# display.net
KiCad netlist of a schematic drawn in Altium Designer
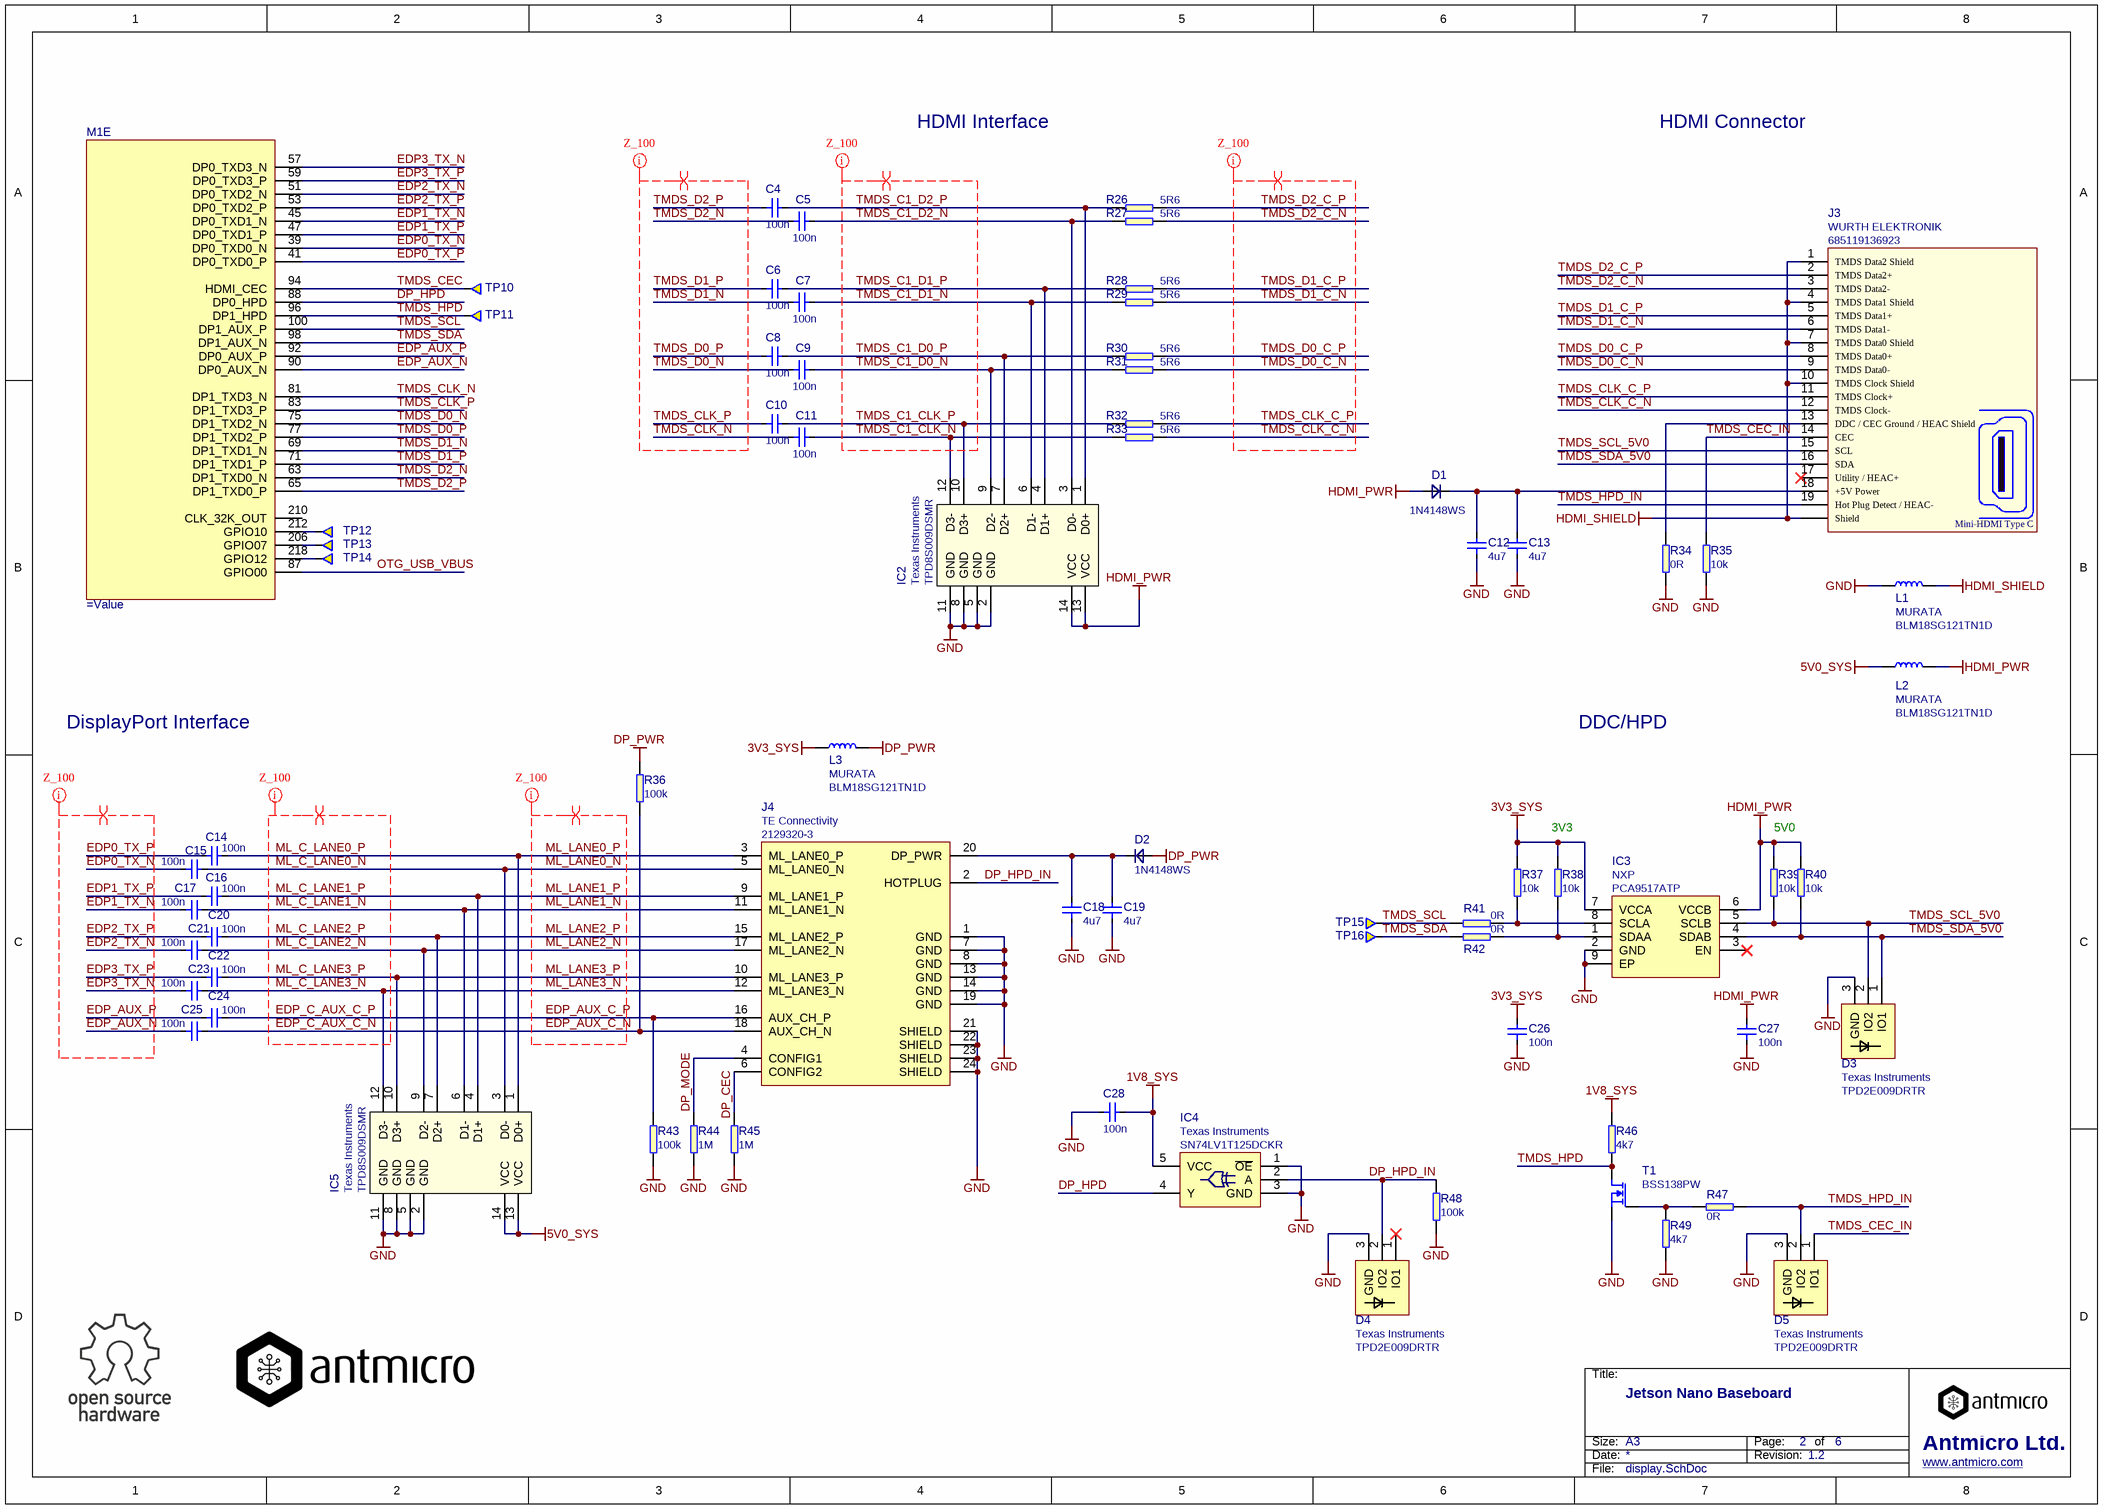
[diagram p0: display.SchDoc]

(export (version "E")
  (design (tool "Eeschema 10.0.6"))
  (components
    (comp (ref "C4")
      (value "100n")
      (footprint "0402")
      (description "MLCC SMT Capacitor 100n 0402")
      (fields (field (name "MANUFACTURER") "TDK") (field (name "PARTNUMBER") "C_100n_0402"))
      (libsource (lib "jetson-nano-baseboard") (part "C_100n_0402"))
    )
    (comp (ref "C5")
      (value "100n")
      (footprint "0402")
      (description "MLCC SMT Capacitor 100n 0402")
      (fields (field (name "MANUFACTURER") "TDK") (field (name "PARTNUMBER") "C_100n_0402"))
      (libsource (lib "jetson-nano-baseboard") (part "C_100n_0402"))
    )
    (comp (ref "C6")
      (value "100n")
      (footprint "0402")
      (description "MLCC SMT Capacitor 100n 0402")
      (fields (field (name "MANUFACTURER") "TDK") (field (name "PARTNUMBER") "C_100n_0402"))
      (libsource (lib "jetson-nano-baseboard") (part "C_100n_0402"))
    )
    (comp (ref "C7")
      (value "100n")
      (footprint "0402")
      (description "MLCC SMT Capacitor 100n 0402")
      (fields (field (name "MANUFACTURER") "TDK") (field (name "PARTNUMBER") "C_100n_0402"))
      (libsource (lib "jetson-nano-baseboard") (part "C_100n_0402"))
    )
    (comp (ref "C8")
      (value "100n")
      (footprint "0402")
      (description "MLCC SMT Capacitor 100n 0402")
      (fields (field (name "MANUFACTURER") "TDK") (field (name "PARTNUMBER") "C_100n_0402"))
      (libsource (lib "jetson-nano-baseboard") (part "C_100n_0402"))
    )
    (comp (ref "C9")
      (value "100n")
      (footprint "0402")
      (description "MLCC SMT Capacitor 100n 0402")
      (fields (field (name "MANUFACTURER") "TDK") (field (name "PARTNUMBER") "C_100n_0402"))
      (libsource (lib "jetson-nano-baseboard") (part "C_100n_0402"))
    )
    (comp (ref "C10")
      (value "100n")
      (footprint "0402")
      (description "MLCC SMT Capacitor 100n 0402")
      (fields (field (name "MANUFACTURER") "TDK") (field (name "PARTNUMBER") "C_100n_0402"))
      (libsource (lib "jetson-nano-baseboard") (part "C_100n_0402"))
    )
    (comp (ref "C11")
      (value "100n")
      (footprint "0402")
      (description "MLCC SMT Capacitor 100n 0402")
      (fields (field (name "MANUFACTURER") "TDK") (field (name "PARTNUMBER") "C_100n_0402"))
      (libsource (lib "jetson-nano-baseboard") (part "C_100n_0402"))
    )
    (comp (ref "C12")
      (value "4u7")
      (footprint "0402")
      (description "MLCC SMT Capacitor 4.7uF 0402")
      (fields (field (name "PARTNUMBER") "C_4u7_0402") (field (name "MANUFACTURER") "MURATA"))
      (libsource (lib "jetson-nano-baseboard") (part "C_4u7_0402"))
    )
    (comp (ref "C13")
      (value "4u7")
      (footprint "0402")
      (description "MLCC SMT Capacitor 4.7uF 0402")
      (fields (field (name "PARTNUMBER") "C_4u7_0402") (field (name "MANUFACTURER") "MURATA"))
      (libsource (lib "jetson-nano-baseboard") (part "C_4u7_0402"))
    )
    (comp (ref "C14")
      (value "100n")
      (footprint "0402")
      (description "MLCC SMT Capacitor 100n 0402")
      (fields (field (name "MANUFACTURER") "TDK") (field (name "PARTNUMBER") "C_100n_0402"))
      (libsource (lib "jetson-nano-baseboard") (part "C_100n_0402"))
    )
    (comp (ref "C15")
      (value "100n")
      (footprint "0402")
      (description "MLCC SMT Capacitor 100n 0402")
      (fields (field (name "MANUFACTURER") "TDK") (field (name "PARTNUMBER") "C_100n_0402"))
      (libsource (lib "jetson-nano-baseboard") (part "C_100n_0402"))
    )
    (comp (ref "C16")
      (value "100n")
      (footprint "0402")
      (description "MLCC SMT Capacitor 100n 0402")
      (fields (field (name "MANUFACTURER") "TDK") (field (name "PARTNUMBER") "C_100n_0402"))
      (libsource (lib "jetson-nano-baseboard") (part "C_100n_0402"))
    )
    (comp (ref "C17")
      (value "100n")
      (footprint "0402")
      (description "MLCC SMT Capacitor 100n 0402")
      (fields (field (name "MANUFACTURER") "TDK") (field (name "PARTNUMBER") "C_100n_0402"))
      (libsource (lib "jetson-nano-baseboard") (part "C_100n_0402"))
    )
    (comp (ref "C18")
      (value "4u7")
      (footprint "0402")
      (description "MLCC SMT Capacitor 4.7uF 0402")
      (fields (field (name "PARTNUMBER") "C_4u7_0402") (field (name "MANUFACTURER") "MURATA"))
      (libsource (lib "jetson-nano-baseboard") (part "C_4u7_0402"))
    )
    (comp (ref "C19")
      (value "4u7")
      (footprint "0402")
      (description "MLCC SMT Capacitor 4.7uF 0402")
      (fields (field (name "PARTNUMBER") "C_4u7_0402") (field (name "MANUFACTURER") "MURATA"))
      (libsource (lib "jetson-nano-baseboard") (part "C_4u7_0402"))
    )
    (comp (ref "C20")
      (value "100n")
      (footprint "0402")
      (description "MLCC SMT Capacitor 100n 0402")
      (fields (field (name "MANUFACTURER") "TDK") (field (name "PARTNUMBER") "C_100n_0402"))
      (libsource (lib "jetson-nano-baseboard") (part "C_100n_0402"))
    )
    (comp (ref "C21")
      (value "100n")
      (footprint "0402")
      (description "MLCC SMT Capacitor 100n 0402")
      (fields (field (name "MANUFACTURER") "TDK") (field (name "PARTNUMBER") "C_100n_0402"))
      (libsource (lib "jetson-nano-baseboard") (part "C_100n_0402"))
    )
    (comp (ref "C22")
      (value "100n")
      (footprint "0402")
      (description "MLCC SMT Capacitor 100n 0402")
      (fields (field (name "MANUFACTURER") "TDK") (field (name "PARTNUMBER") "C_100n_0402"))
      (libsource (lib "jetson-nano-baseboard") (part "C_100n_0402"))
    )
    (comp (ref "C23")
      (value "100n")
      (footprint "0402")
      (description "MLCC SMT Capacitor 100n 0402")
      (fields (field (name "MANUFACTURER") "TDK") (field (name "PARTNUMBER") "C_100n_0402"))
      (libsource (lib "jetson-nano-baseboard") (part "C_100n_0402"))
    )
    (comp (ref "C24")
      (value "100n")
      (footprint "0402")
      (description "MLCC SMT Capacitor 100n 0402")
      (fields (field (name "MANUFACTURER") "TDK") (field (name "PARTNUMBER") "C_100n_0402"))
      (libsource (lib "jetson-nano-baseboard") (part "C_100n_0402"))
    )
    (comp (ref "C25")
      (value "100n")
      (footprint "0402")
      (description "MLCC SMT Capacitor 100n 0402")
      (fields (field (name "MANUFACTURER") "TDK") (field (name "PARTNUMBER") "C_100n_0402"))
      (libsource (lib "jetson-nano-baseboard") (part "C_100n_0402"))
    )
    (comp (ref "C26")
      (value "100n")
      (footprint "0603")
      (description "MLCC SMT Capacitor 100nF 0603")
      (fields (field (name "MANUFACTURER") "AVX") (field (name "PARTNUMBER") "C_100n_0603"))
      (libsource (lib "jetson-nano-baseboard") (part "C_100n_0603"))
    )
    (comp (ref "C27")
      (value "100n")
      (footprint "0603")
      (description "MLCC SMT Capacitor 100nF 0603")
      (fields (field (name "MANUFACTURER") "AVX") (field (name "PARTNUMBER") "C_100n_0603"))
      (libsource (lib "jetson-nano-baseboard") (part "C_100n_0603"))
    )
    (comp (ref "C28")
      (value "100n")
      (footprint "0603")
      (description "MLCC SMT Capacitor 100nF 0603")
      (fields (field (name "MANUFACTURER") "AVX") (field (name "PARTNUMBER") "C_100n_0603"))
      (libsource (lib "jetson-nano-baseboard") (part "C_100n_0603"))
    )
    (comp (ref "D1")
      (value "1N4148WS")
      (footprint "SOD-323")
      (description "Diode small signal")
      (fields (field (name "MANUFACTURER") "ON SEMICONDUCTOR"))
      (libsource (lib "jetson-nano-baseboard") (part "diode"))
    )
    (comp (ref "D2")
      (value "1N4148WS")
      (footprint "SOD-323")
      (description "Diode small signal")
      (fields (field (name "MANUFACTURER") "ON SEMICONDUCTOR"))
      (libsource (lib "jetson-nano-baseboard") (part "diode"))
    )
    (comp (ref "D3")
      (value "TPD2E009DRTR")
      (footprint "SOT-3")
      (description "ESD Suppressors 2-CH")
      (fields (field (name "MANUFACTURER") "Texas Instruments"))
      (libsource (lib "jetson-nano-baseboard") (part "TPD2E009"))
    )
    (comp (ref "D4")
      (value "TPD2E009DRTR")
      (footprint "SOT-3")
      (description "ESD Suppressors 2-CH")
      (fields (field (name "MANUFACTURER") "Texas Instruments"))
      (libsource (lib "jetson-nano-baseboard") (part "TPD2E009"))
    )
    (comp (ref "D5")
      (value "TPD2E009DRTR")
      (footprint "SOT-3")
      (description "ESD Suppressors 2-CH")
      (fields (field (name "MANUFACTURER") "Texas Instruments"))
      (libsource (lib "jetson-nano-baseboard") (part "TPD2E009"))
    )
    (comp (ref "IC2")
      (value "TPD8S009")
      (footprint "SON-15")
      (description "8-Channel ESD Protection for DisplayPort and HDMI")
      (fields (field (name "MANUFACTURER") "Texas Instruments") (field (name "PARTSYMBOL") "TPD8S009DSMR"))
      (libsource (lib "jetson-nano-baseboard") (part "TPD8S009"))
    )
    (comp (ref "IC3")
      (value "PCA9517ATP")
      (footprint "PCA9517ATP")
      (description "I2C BUS REPEATER W/ LEVEL TRANS, HWSON-8")
      (fields (field (name "MANUFACTURER") "NXP"))
      (libsource (lib "jetson-nano-baseboard") (part "PCA9517ATP"))
    )
    (comp (ref "IC4")
      (value "SN74LV1T125DCKR")
      (footprint "SC70-5")
      (description "Buffer, 74LV1T125, 1.6 V to 5.5 V, SOT-23-5")
      (fields (field (name "MANUFACTURER") "Texas Instruments"))
      (libsource (lib "jetson-nano-baseboard") (part "SN74LV1T125"))
    )
    (comp (ref "IC5")
      (value "TPD8S009")
      (footprint "SON-15")
      (description "8-Channel ESD Protection for DisplayPort and HDMI")
      (fields (field (name "MANUFACTURER") "Texas Instruments") (field (name "PARTSYMBOL") "TPD8S009DSMR"))
      (libsource (lib "jetson-nano-baseboard") (part "TPD8S009"))
    )
    (comp (ref "J3")
      (value "685119136923")
      (footprint "WE_685119136923")
      (description "CONN HDMI FEMALE R/A 19POS 2.6MM")
      (fields (field (name "PARTNUMBER") "WE_685119136923") (field (name "MANUFACTURER") "WURTH ELEKTRONIK"))
      (libsource (lib "jetson-nano-baseboard") (part "WE_685119136923"))
    )
    (comp (ref "J4")
      (value "2129320-3")
      (footprint "2129320-3")
      (description "Mini Displayport Reverse Offset")
      (fields (field (name "MANUFACTURER") "TE Connectivity"))
      (libsource (lib "jetson-nano-baseboard") (part "miniDP"))
    )
    (comp (ref "L1")
      (value "BLM18SG121TN1D")
      (footprint "0603")
      (description "FERRITE BEAD, 0.025OHM, 3A, 0603")
      (fields (field (name "MANUFACTURER") "MURATA"))
      (libsource (lib "jetson-nano-baseboard") (part "BLM18SG121TN1D"))
    )
    (comp (ref "L2")
      (value "BLM18SG121TN1D")
      (footprint "0603")
      (description "FERRITE BEAD, 0.025OHM, 3A, 0603")
      (fields (field (name "MANUFACTURER") "MURATA"))
      (libsource (lib "jetson-nano-baseboard") (part "BLM18SG121TN1D"))
    )
    (comp (ref "L3")
      (value "BLM18SG121TN1D")
      (footprint "0603")
      (description "FERRITE BEAD, 0.025OHM, 3A, 0603")
      (fields (field (name "MANUFACTURER") "MURATA"))
      (libsource (lib "jetson-nano-baseboard") (part "BLM18SG121TN1D"))
    )
    (comp (ref "M1")
      (value "~")
      (footprint "jetson-nano-connector")
      (fields (field (name "PARTNUMBER") "jetson-nano-new-release"))
      (libsource (lib "jetson-nano-baseboard") (part "Jetson-Nano-new-release"))
    )
    (comp (ref "R26")
      (value "5R6")
      (footprint "0402")
      (description "RES, 5R6, 0402")
      (fields (field (name "PARTNUMBER") "R_5R6_0402") (field (name "MANUFACTURER") "Panasonic"))
      (libsource (lib "jetson-nano-baseboard") (part "R_5R6_0402"))
    )
    (comp (ref "R27")
      (value "5R6")
      (footprint "0402")
      (description "RES, 5R6, 0402")
      (fields (field (name "PARTNUMBER") "R_5R6_0402") (field (name "MANUFACTURER") "Panasonic"))
      (libsource (lib "jetson-nano-baseboard") (part "R_5R6_0402"))
    )
    (comp (ref "R28")
      (value "5R6")
      (footprint "0402")
      (description "RES, 5R6, 0402")
      (fields (field (name "PARTNUMBER") "R_5R6_0402") (field (name "MANUFACTURER") "Panasonic"))
      (libsource (lib "jetson-nano-baseboard") (part "R_5R6_0402"))
    )
    (comp (ref "R29")
      (value "5R6")
      (footprint "0402")
      (description "RES, 5R6, 0402")
      (fields (field (name "PARTNUMBER") "R_5R6_0402") (field (name "MANUFACTURER") "Panasonic"))
      (libsource (lib "jetson-nano-baseboard") (part "R_5R6_0402"))
    )
    (comp (ref "R30")
      (value "5R6")
      (footprint "0402")
      (description "RES, 5R6, 0402")
      (fields (field (name "PARTNUMBER") "R_5R6_0402") (field (name "MANUFACTURER") "Panasonic"))
      (libsource (lib "jetson-nano-baseboard") (part "R_5R6_0402"))
    )
    (comp (ref "R31")
      (value "5R6")
      (footprint "0402")
      (description "RES, 5R6, 0402")
      (fields (field (name "PARTNUMBER") "R_5R6_0402") (field (name "MANUFACTURER") "Panasonic"))
      (libsource (lib "jetson-nano-baseboard") (part "R_5R6_0402"))
    )
    (comp (ref "R32")
      (value "5R6")
      (footprint "0402")
      (description "RES, 5R6, 0402")
      (fields (field (name "PARTNUMBER") "R_5R6_0402") (field (name "MANUFACTURER") "Panasonic"))
      (libsource (lib "jetson-nano-baseboard") (part "R_5R6_0402"))
    )
    (comp (ref "R33")
      (value "5R6")
      (footprint "0402")
      (description "RES, 5R6, 0402")
      (fields (field (name "PARTNUMBER") "R_5R6_0402") (field (name "MANUFACTURER") "Panasonic"))
      (libsource (lib "jetson-nano-baseboard") (part "R_5R6_0402"))
    )
    (comp (ref "R34")
      (value "0R")
      (footprint "0402")
      (description "RES, 0R, 0402")
      (fields (field (name "PARTNUMBER") "R_0R_0402") (field (name "MANUFACTURER") "Panasonic"))
      (libsource (lib "") (part "R_0R_0402_1"))
    )
    (comp (ref "R35")
      (value "10k")
      (footprint "0402")
      (description "RES, 10k, 0402")
      (fields (field (name "MANUFACTURER") "MULTICOMP") (field (name "PARTNUMBER") "R_10k_0402"))
      (libsource (lib "jetson-nano-baseboard") (part "R_10k_0402"))
    )
    (comp (ref "R36")
      (value "100k")
      (footprint "0603")
      (description "RES, 100k, 0603")
      (fields (field (name "MANUFACTURER") "BOURNS") (field (name "PARTNUMBER") "R_100k_0603"))
      (libsource (lib "") (part "R_100k_0603_1"))
    )
    (comp (ref "R37")
      (value "10k")
      (footprint "0603")
      (description "RES, 10k, 0603")
      (fields (field (name "MANUFACTURER") "BOURNS") (field (name "PARTNUMBER") "R_10k_0603"))
      (libsource (lib "jetson-nano-baseboard") (part "R_10k_0603"))
    )
    (comp (ref "R38")
      (value "10k")
      (footprint "0603")
      (description "RES, 10k, 0603")
      (fields (field (name "MANUFACTURER") "BOURNS") (field (name "PARTNUMBER") "R_10k_0603"))
      (libsource (lib "jetson-nano-baseboard") (part "R_10k_0603"))
    )
    (comp (ref "R39")
      (value "10k")
      (footprint "0603")
      (description "RES, 10k, 0603")
      (fields (field (name "MANUFACTURER") "BOURNS") (field (name "PARTNUMBER") "R_10k_0603"))
      (libsource (lib "jetson-nano-baseboard") (part "R_10k_0603"))
    )
    (comp (ref "R40")
      (value "10k")
      (footprint "0603")
      (description "RES, 10k, 0603")
      (fields (field (name "MANUFACTURER") "BOURNS") (field (name "PARTNUMBER") "R_10k_0603"))
      (libsource (lib "jetson-nano-baseboard") (part "R_10k_0603"))
    )
    (comp (ref "R41")
      (value "0R")
      (footprint "0402")
      (description "RES, 0R, 0402")
      (fields (field (name "PARTNUMBER") "R_0R_0402") (field (name "MANUFACTURER") "Panasonic"))
      (libsource (lib "jetson-nano-baseboard") (part "R_0R_0402"))
    )
    (comp (ref "R42")
      (value "0R")
      (footprint "0402")
      (description "RES, 0R, 0402")
      (fields (field (name "PARTNUMBER") "R_0R_0402") (field (name "MANUFACTURER") "Panasonic"))
      (libsource (lib "jetson-nano-baseboard") (part "R_0R_0402"))
    )
    (comp (ref "R43")
      (value "100k")
      (footprint "0603")
      (description "RES, 100k, 0603")
      (fields (field (name "MANUFACTURER") "BOURNS") (field (name "PARTNUMBER") "R_100k_0603"))
      (libsource (lib "jetson-nano-baseboard") (part "R_100k_0603"))
    )
    (comp (ref "R44")
      (value "1M")
      (footprint "0603")
      (description "RES, 1M, 0603")
      (fields (field (name "MANUFACTURER") "BOURNS") (field (name "PARTNUMBER") "R_1M_0603"))
      (libsource (lib "jetson-nano-baseboard") (part "R_1M_0603"))
    )
    (comp (ref "R45")
      (value "1M")
      (footprint "0603")
      (description "RES, 1M, 0603")
      (fields (field (name "MANUFACTURER") "BOURNS") (field (name "PARTNUMBER") "R_1M_0603"))
      (libsource (lib "jetson-nano-baseboard") (part "R_1M_0603"))
    )
    (comp (ref "R46")
      (value "4k7")
      (footprint "0603")
      (description "RES, 4k7, 0603")
      (fields (field (name "MANUFACTURER") "BOURNS") (field (name "PARTNUMBER") "R_4k7_0603"))
      (libsource (lib "jetson-nano-baseboard") (part "R_4k7_0603"))
    )
    (comp (ref "R47")
      (value "0R")
      (footprint "0402")
      (description "RES, 0R, 0402")
      (fields (field (name "PARTNUMBER") "R_0R_0402") (field (name "MANUFACTURER") "Panasonic"))
      (libsource (lib "jetson-nano-baseboard") (part "R_0R_0402"))
    )
    (comp (ref "R48")
      (value "100k")
      (footprint "0603")
      (description "RES, 100k, 0603")
      (fields (field (name "MANUFACTURER") "BOURNS") (field (name "PARTNUMBER") "R_100k_0603"))
      (libsource (lib "") (part "R_100k_0603_1"))
    )
    (comp (ref "R49")
      (value "4k7")
      (footprint "0603")
      (description "RES, 4k7, 0603")
      (fields (field (name "MANUFACTURER") "BOURNS") (field (name "PARTNUMBER") "R_4k7_0603"))
      (libsource (lib "jetson-nano-baseboard") (part "R_4k7_0603"))
    )
    (comp (ref "T1")
      (value "BSS138PW")
      (footprint "SC70-3")
      (description "MOSFET, N CH, 60V, 0.2A")
      (fields (field (name "MANUFACTURER") "NXP"))
      (libsource (lib "jetson-nano-baseboard") (part "NMOS"))
    )
    (comp (ref "TP10")
      (value "Testpad")
      (footprint "TP-R-1.5")
      (description "Testpad, round, 1.5mm")
      (fields (field (name "PARTNUMBER") "TP-R-1.5"))
      (libsource (lib "jetson-nano-baseboard") (part "Testpad"))
    )
    (comp (ref "TP11")
      (value "Testpad")
      (footprint "TP-R-1.5")
      (description "Testpad, round, 1.5mm")
      (fields (field (name "PARTNUMBER") "TP-R-1.5"))
      (libsource (lib "jetson-nano-baseboard") (part "Testpad"))
    )
    (comp (ref "TP12")
      (value "Testpad")
      (footprint "TP-R-1.5")
      (description "Testpad, round, 1.5mm")
      (fields (field (name "PARTNUMBER") "TP-R-1.5"))
      (libsource (lib "jetson-nano-baseboard") (part "Testpad"))
    )
    (comp (ref "TP13")
      (value "Testpad")
      (footprint "TP-R-1.5")
      (description "Testpad, round, 1.5mm")
      (fields (field (name "PARTNUMBER") "TP-R-1.5"))
      (libsource (lib "jetson-nano-baseboard") (part "Testpad"))
    )
    (comp (ref "TP14")
      (value "Testpad")
      (footprint "TP-R-1.5")
      (description "Testpad, round, 1.5mm")
      (fields (field (name "PARTNUMBER") "TP-R-1.5"))
      (libsource (lib "jetson-nano-baseboard") (part "Testpad"))
    )
    (comp (ref "TP15")
      (value "Testpad")
      (footprint "TP-R-1.5")
      (description "Testpad, round, 1.5mm")
      (fields (field (name "PARTNUMBER") "TP-R-1.5"))
      (libsource (lib "jetson-nano-baseboard") (part "Testpad"))
    )
    (comp (ref "TP16")
      (value "Testpad")
      (footprint "TP-R-1.5")
      (description "Testpad, round, 1.5mm")
      (fields (field (name "PARTNUMBER") "TP-R-1.5"))
      (libsource (lib "jetson-nano-baseboard") (part "Testpad"))
    )
  )
  (nets
    (net (code "2") (name "/DP_HPD") (class "Default")
      (node (ref "IC4") (pin "4") (pinfunction "Y_4") (pintype "passive"))
      (node (ref "M1") (pin "88") (pinfunction "DP0_HPD_88") (pintype "passive"))
    )
    (net (code "3") (name "/DP_HPD_IN") (class "Default")
      (node (ref "D4") (pin "2") (pinfunction "IO2_2") (pintype "passive"))
      (node (ref "IC4") (pin "2") (pinfunction "A_2") (pintype "passive"))
      (node (ref "J4") (pin "2") (pinfunction "HOTPLUG_2") (pintype "passive"))
      (node (ref "R48") (pin "1") (pintype "passive"))
    )
    (net (code "4") (name "/DP_MODE") (class "Default")
      (node (ref "J4") (pin "4") (pinfunction "CONFIG1_4") (pintype "passive"))
      (node (ref "R44") (pin "2") (pintype "passive"))
    )
    (net (code "5") (name "/EDP0_TX_N") (class "Default")
      (node (ref "C15") (pin "1") (pinfunction "1_1") (pintype "passive"))
      (node (ref "M1") (pin "39") (pinfunction "DP0_TXD0_N_39") (pintype "passive"))
    )
    (net (code "6") (name "/EDP0_TX_P") (class "Default")
      (node (ref "C14") (pin "1") (pinfunction "1_1") (pintype "passive"))
      (node (ref "M1") (pin "41") (pinfunction "DP0_TXD0_P_41") (pintype "passive"))
    )
    (net (code "7") (name "/EDP1_TX_N") (class "Default")
      (node (ref "C17") (pin "1") (pinfunction "1_1") (pintype "passive"))
      (node (ref "M1") (pin "45") (pinfunction "DP0_TXD1_N_45") (pintype "passive"))
    )
    (net (code "8") (name "/EDP1_TX_P") (class "Default")
      (node (ref "C16") (pin "1") (pinfunction "1_1") (pintype "passive"))
      (node (ref "M1") (pin "47") (pinfunction "DP0_TXD1_P_47") (pintype "passive"))
    )
    (net (code "9") (name "/EDP2_TX_N") (class "Default")
      (node (ref "C21") (pin "1") (pinfunction "1_1") (pintype "passive"))
      (node (ref "M1") (pin "51") (pinfunction "DP0_TXD2_N_51") (pintype "passive"))
    )
    (net (code "10") (name "/EDP2_TX_P") (class "Default")
      (node (ref "C20") (pin "1") (pinfunction "1_1") (pintype "passive"))
      (node (ref "M1") (pin "53") (pinfunction "DP0_TXD2_P_53") (pintype "passive"))
    )
    (net (code "11") (name "/EDP3_TX_N") (class "Default")
      (node (ref "C22") (pin "1") (pinfunction "1_1") (pintype "passive"))
      (node (ref "M1") (pin "57") (pinfunction "DP0_TXD3_N_57") (pintype "passive"))
    )
    (net (code "12") (name "/EDP3_TX_P") (class "Default")
      (node (ref "C23") (pin "1") (pinfunction "1_1") (pintype "passive"))
      (node (ref "M1") (pin "59") (pinfunction "DP0_TXD3_P_59") (pintype "passive"))
    )
    (net (code "13") (name "/EDP_AUX_C_N") (class "Default")
      (node (ref "C25") (pin "2") (pinfunction "2_2") (pintype "passive"))
      (node (ref "J4") (pin "18") (pinfunction "AUX_CH_N_18") (pintype "passive"))
      (node (ref "R36") (pin "2") (pintype "passive"))
    )
    (net (code "14") (name "/EDP_AUX_C_P") (class "Default")
      (node (ref "C24") (pin "2") (pinfunction "2_2") (pintype "passive"))
      (node (ref "J4") (pin "16") (pinfunction "AUX_CH_P_16") (pintype "passive"))
      (node (ref "R43") (pin "2") (pintype "passive"))
    )
    (net (code "15") (name "/EDP_AUX_N") (class "Default")
      (node (ref "C25") (pin "1") (pinfunction "1_1") (pintype "passive"))
      (node (ref "M1") (pin "90") (pinfunction "DP0_AUX_N_90") (pintype "passive"))
    )
    (net (code "16") (name "/EDP_AUX_P") (class "Default")
      (node (ref "C24") (pin "1") (pinfunction "1_1") (pintype "passive"))
      (node (ref "M1") (pin "92") (pinfunction "DP0_AUX_P_92") (pintype "passive"))
    )
    (net (code "17") (name "/ML_C_LANE0_N") (class "Default")
      (node (ref "C15") (pin "2") (pinfunction "2_2") (pintype "passive"))
      (node (ref "IC5") (pin "3") (pinfunction "D0-_3") (pintype "passive"))
      (node (ref "J4") (pin "5") (pinfunction "ML_LANE0_N_5") (pintype "passive"))
    )
    (net (code "18") (name "/ML_C_LANE0_P") (class "Default")
      (node (ref "C14") (pin "2") (pinfunction "2_2") (pintype "passive"))
      (node (ref "IC5") (pin "1") (pinfunction "D0+_1") (pintype "passive"))
      (node (ref "J4") (pin "3") (pinfunction "ML_LANE0_P_3") (pintype "passive"))
    )
    (net (code "19") (name "/ML_C_LANE1_N") (class "Default")
      (node (ref "C17") (pin "2") (pinfunction "2_2") (pintype "passive"))
      (node (ref "IC5") (pin "6") (pinfunction "D1-_6") (pintype "passive"))
      (node (ref "J4") (pin "11") (pinfunction "ML_LANE1_N_11") (pintype "passive"))
    )
    (net (code "20") (name "/ML_C_LANE1_P") (class "Default")
      (node (ref "C16") (pin "2") (pinfunction "2_2") (pintype "passive"))
      (node (ref "IC5") (pin "4") (pinfunction "D1+_4") (pintype "passive"))
      (node (ref "J4") (pin "9") (pinfunction "ML_LANE1_P_9") (pintype "passive"))
    )
    (net (code "21") (name "/ML_C_LANE2_N") (class "Default")
      (node (ref "C21") (pin "2") (pinfunction "2_2") (pintype "passive"))
      (node (ref "IC5") (pin "9") (pinfunction "D2-_9") (pintype "passive"))
      (node (ref "J4") (pin "17") (pinfunction "ML_LANE2_N_17") (pintype "passive"))
    )
    (net (code "22") (name "/ML_C_LANE2_P") (class "Default")
      (node (ref "C20") (pin "2") (pinfunction "2_2") (pintype "passive"))
      (node (ref "IC5") (pin "7") (pinfunction "D2+_7") (pintype "passive"))
      (node (ref "J4") (pin "15") (pinfunction "ML_LANE2_P_15") (pintype "passive"))
    )
    (net (code "23") (name "/ML_C_LANE3_N") (class "Default")
      (node (ref "C22") (pin "2") (pinfunction "2_2") (pintype "passive"))
      (node (ref "IC5") (pin "12") (pinfunction "D3-_12") (pintype "passive"))
      (node (ref "J4") (pin "12") (pinfunction "ML_LANE3_N_12") (pintype "passive"))
    )
    (net (code "24") (name "/ML_C_LANE3_P") (class "Default")
      (node (ref "C23") (pin "2") (pinfunction "2_2") (pintype "passive"))
      (node (ref "IC5") (pin "10") (pinfunction "D3+_10") (pintype "passive"))
      (node (ref "J4") (pin "10") (pinfunction "ML_LANE3_P_10") (pintype "passive"))
    )
    (net (code "25") (name "/OTG_USB_VBUS") (class "Default")
      (node (ref "M1") (pin "87") (pinfunction "GPIO00_87") (pintype "passive"))
    )
    (net (code "26") (name "/TMDS_C1_CLK_N") (class "Default")
      (node (ref "C11") (pin "2") (pinfunction "2_2") (pintype "passive"))
      (node (ref "IC2") (pin "12") (pinfunction "D3-_12") (pintype "passive"))
      (node (ref "R33") (pin "1") (pintype "passive"))
    )
    (net (code "27") (name "/TMDS_C1_CLK_P") (class "Default")
      (node (ref "C10") (pin "2") (pinfunction "2_2") (pintype "passive"))
      (node (ref "IC2") (pin "10") (pinfunction "D3+_10") (pintype "passive"))
      (node (ref "R32") (pin "1") (pintype "passive"))
    )
    (net (code "28") (name "/TMDS_C1_D0_N") (class "Default")
      (node (ref "C9") (pin "2") (pinfunction "2_2") (pintype "passive"))
      (node (ref "IC2") (pin "9") (pinfunction "D2-_9") (pintype "passive"))
      (node (ref "R31") (pin "1") (pintype "passive"))
    )
    (net (code "29") (name "/TMDS_C1_D0_P") (class "Default")
      (node (ref "C8") (pin "2") (pinfunction "2_2") (pintype "passive"))
      (node (ref "IC2") (pin "7") (pinfunction "D2+_7") (pintype "passive"))
      (node (ref "R30") (pin "1") (pintype "passive"))
    )
    (net (code "30") (name "/TMDS_C1_D1_N") (class "Default")
      (node (ref "C7") (pin "2") (pinfunction "2_2") (pintype "passive"))
      (node (ref "IC2") (pin "6") (pinfunction "D1-_6") (pintype "passive"))
      (node (ref "R29") (pin "1") (pintype "passive"))
    )
    (net (code "31") (name "/TMDS_C1_D1_P") (class "Default")
      (node (ref "C6") (pin "2") (pinfunction "2_2") (pintype "passive"))
      (node (ref "IC2") (pin "4") (pinfunction "D1+_4") (pintype "passive"))
      (node (ref "R28") (pin "1") (pintype "passive"))
    )
    (net (code "32") (name "/TMDS_C1_D2_N") (class "Default")
      (node (ref "C5") (pin "2") (pinfunction "2_2") (pintype "passive"))
      (node (ref "IC2") (pin "3") (pinfunction "D0-_3") (pintype "passive"))
      (node (ref "R27") (pin "1") (pintype "passive"))
    )
    (net (code "33") (name "/TMDS_C1_D2_P") (class "Default")
      (node (ref "C4") (pin "2") (pinfunction "2_2") (pintype "passive"))
      (node (ref "IC2") (pin "1") (pinfunction "D0+_1") (pintype "passive"))
      (node (ref "R26") (pin "1") (pintype "passive"))
    )
    (net (code "34") (name "/TMDS_CEC") (class "Default")
      (node (ref "M1") (pin "94") (pinfunction "HDMI_CEC_94") (pintype "passive"))
      (node (ref "TP10") (pin "1") (pintype "passive"))
    )
    (net (code "35") (name "/TMDS_CEC_IN") (class "Default")
      (node (ref "D5") (pin "1") (pinfunction "IO1_1") (pintype "passive"))
      (node (ref "J3") (pin "14") (pinfunction "CEC_14") (pintype "passive"))
      (node (ref "R35") (pin "2") (pintype "passive"))
    )
    (net (code "36") (name "/TMDS_CLK_C_N") (class "Default")
      (node (ref "J3") (pin "12") (pinfunction "TMDS_Clock-_12") (pintype "passive"))
      (node (ref "R33") (pin "2") (pintype "passive"))
    )
    (net (code "37") (name "/TMDS_CLK_C_P") (class "Default")
      (node (ref "J3") (pin "11") (pinfunction "TMDS_Clock+_11") (pintype "passive"))
      (node (ref "R32") (pin "2") (pintype "passive"))
    )
    (net (code "38") (name "/TMDS_CLK_N") (class "Default")
      (node (ref "C11") (pin "1") (pinfunction "1_1") (pintype "passive"))
      (node (ref "M1") (pin "81") (pinfunction "DP1_TXD3_N_81") (pintype "passive"))
    )
    (net (code "39") (name "/TMDS_CLK_P") (class "Default")
      (node (ref "C10") (pin "1") (pinfunction "1_1") (pintype "passive"))
      (node (ref "M1") (pin "83") (pinfunction "DP1_TXD3_P_83") (pintype "passive"))
    )
    (net (code "40") (name "/TMDS_D0_C_N") (class "Default")
      (node (ref "J3") (pin "9") (pinfunction "TMDS_Data0-_9") (pintype "passive"))
      (node (ref "R31") (pin "2") (pintype "passive"))
    )
    (net (code "41") (name "/TMDS_D0_C_P") (class "Default")
      (node (ref "J3") (pin "8") (pinfunction "TMDS_Data0+_8") (pintype "passive"))
      (node (ref "R30") (pin "2") (pintype "passive"))
    )
    (net (code "42") (name "/TMDS_D0_N") (class "Default")
      (node (ref "C9") (pin "1") (pinfunction "1_1") (pintype "passive"))
      (node (ref "M1") (pin "75") (pinfunction "DP1_TXD2_N_75") (pintype "passive"))
    )
    (net (code "43") (name "/TMDS_D0_P") (class "Default")
      (node (ref "C8") (pin "1") (pinfunction "1_1") (pintype "passive"))
      (node (ref "M1") (pin "77") (pinfunction "DP1_TXD2_P_77") (pintype "passive"))
    )
    (net (code "44") (name "/TMDS_D1_C_N") (class "Default")
      (node (ref "J3") (pin "6") (pinfunction "TMDS_Data1-_6") (pintype "passive"))
      (node (ref "R29") (pin "2") (pintype "passive"))
    )
    (net (code "45") (name "/TMDS_D1_C_P") (class "Default")
      (node (ref "J3") (pin "5") (pinfunction "TMDS_Data1+_5") (pintype "passive"))
      (node (ref "R28") (pin "2") (pintype "passive"))
    )
    (net (code "46") (name "/TMDS_D1_N") (class "Default")
      (node (ref "C7") (pin "1") (pinfunction "1_1") (pintype "passive"))
      (node (ref "M1") (pin "69") (pinfunction "DP1_TXD1_N_69") (pintype "passive"))
    )
    (net (code "47") (name "/TMDS_D1_P") (class "Default")
      (node (ref "C6") (pin "1") (pinfunction "1_1") (pintype "passive"))
      (node (ref "M1") (pin "71") (pinfunction "DP1_TXD1_P_71") (pintype "passive"))
    )
    (net (code "48") (name "/TMDS_D2_C_N") (class "Default")
      (node (ref "J3") (pin "3") (pinfunction "TMDS_Data2-_3") (pintype "passive"))
      (node (ref "R27") (pin "2") (pintype "passive"))
    )
    (net (code "49") (name "/TMDS_D2_C_P") (class "Default")
      (node (ref "J3") (pin "2") (pinfunction "TMDS_Data2+_2") (pintype "passive"))
      (node (ref "R26") (pin "2") (pintype "passive"))
    )
    (net (code "50") (name "/TMDS_D2_N") (class "Default")
      (node (ref "C5") (pin "1") (pinfunction "1_1") (pintype "passive"))
      (node (ref "M1") (pin "63") (pinfunction "DP1_TXD0_N_63") (pintype "passive"))
    )
    (net (code "51") (name "/TMDS_D2_P") (class "Default")
      (node (ref "C4") (pin "1") (pinfunction "1_1") (pintype "passive"))
      (node (ref "M1") (pin "65") (pinfunction "DP1_TXD0_P_65") (pintype "passive"))
    )
    (net (code "52") (name "/TMDS_HPD") (class "Default")
      (node (ref "M1") (pin "96") (pinfunction "DP1_HPD_96") (pintype "passive"))
      (node (ref "R46") (pin "1") (pintype "passive"))
      (node (ref "T1") (pin "3") (pinfunction "D_3") (pintype "passive"))
      (node (ref "TP11") (pin "1") (pintype "passive"))
    )
    (net (code "53") (name "/TMDS_HPD_IN") (class "Default")
      (node (ref "D5") (pin "2") (pinfunction "IO2_2") (pintype "passive"))
      (node (ref "J3") (pin "19") (pinfunction "Hot_Plug_Detect_/_HEAC-_19") (pintype "passive"))
      (node (ref "R47") (pin "1") (pintype "passive"))
    )
    (net (code "54") (name "/TMDS_SCL") (class "Default")
      (node (ref "M1") (pin "100") (pinfunction "DP1_AUX_P_100") (pintype "passive"))
      (node (ref "R41") (pin "2") (pintype "passive"))
      (node (ref "TP15") (pin "1") (pintype "passive"))
    )
    (net (code "55") (name "/TMDS_SCL_5V0") (class "Default")
      (node (ref "D3") (pin "2") (pinfunction "IO2_2") (pintype "passive"))
      (node (ref "IC3") (pin "5") (pinfunction "SCLB_5") (pintype "passive"))
      (node (ref "J3") (pin "15") (pinfunction "SCL_15") (pintype "passive"))
      (node (ref "R39") (pin "1") (pintype "passive"))
    )
    (net (code "56") (name "/TMDS_SDA") (class "Default")
      (node (ref "M1") (pin "98") (pinfunction "DP1_AUX_N_98") (pintype "passive"))
      (node (ref "R42") (pin "2") (pintype "passive"))
      (node (ref "TP16") (pin "1") (pintype "passive"))
    )
    (net (code "57") (name "/TMDS_SDA_5V0") (class "Default")
      (node (ref "D3") (pin "1") (pinfunction "IO1_1") (pintype "passive"))
      (node (ref "IC3") (pin "4") (pinfunction "SDAB_4") (pintype "passive"))
      (node (ref "J3") (pin "16") (pinfunction "SDA_16") (pintype "passive"))
      (node (ref "R40") (pin "1") (pintype "passive"))
    )
    (net (code "58") (name "1V8_SYS") (class "Default")
      (node (ref "C28") (pin "2") (pinfunction "2_2") (pintype "passive"))
      (node (ref "IC4") (pin "5") (pinfunction "VCC_5") (pintype "passive"))
      (node (ref "R46") (pin "2") (pintype "passive"))
    )
    (net (code "59") (name "3V3_SYS") (class "Default")
      (node (ref "C26") (pin "2") (pinfunction "2_2") (pintype "passive"))
      (node (ref "IC3") (pin "7") (pinfunction "VCCA_7") (pintype "passive"))
      (node (ref "L3") (pin "1") (pintype "passive"))
      (node (ref "R37") (pin "2") (pintype "passive"))
      (node (ref "R38") (pin "2") (pintype "passive"))
    )
    (net (code "60") (name "5V0_SYS") (class "Default")
      (node (ref "IC5") (pin "13") (pinfunction "VCC_13") (pintype "passive"))
      (node (ref "IC5") (pin "14") (pinfunction "VCC_14") (pintype "passive"))
      (node (ref "L2") (pin "1") (pintype "passive"))
    )
    (net (code "61") (name "DP_PWR") (class "Default")
      (node (ref "D2") (pin "A") (pinfunction "A_A") (pintype "passive"))
      (node (ref "L3") (pin "2") (pintype "passive"))
      (node (ref "R36") (pin "1") (pintype "passive"))
    )
    (net (code "62") (name "GND") (class "Default")
      (node (ref "C12") (pin "1") (pinfunction "1_1") (pintype "passive"))
      (node (ref "C13") (pin "1") (pinfunction "1_1") (pintype "passive"))
      (node (ref "C18") (pin "1") (pinfunction "1_1") (pintype "passive"))
      (node (ref "C19") (pin "1") (pinfunction "1_1") (pintype "passive"))
      (node (ref "C26") (pin "1") (pinfunction "1_1") (pintype "passive"))
      (node (ref "C27") (pin "1") (pinfunction "1_1") (pintype "passive"))
      (node (ref "C28") (pin "1") (pinfunction "1_1") (pintype "passive"))
      (node (ref "D3") (pin "3") (pinfunction "GND_3") (pintype "passive"))
      (node (ref "D4") (pin "3") (pinfunction "GND_3") (pintype "passive"))
      (node (ref "D5") (pin "3") (pinfunction "GND_3") (pintype "passive"))
      (node (ref "IC2") (pin "11") (pinfunction "GND_11") (pintype "passive"))
      (node (ref "IC2") (pin "2") (pinfunction "GND_2") (pintype "passive"))
      (node (ref "IC2") (pin "5") (pinfunction "GND_5") (pintype "passive"))
      (node (ref "IC2") (pin "8") (pinfunction "GND_8") (pintype "passive"))
      (node (ref "IC3") (pin "2") (pinfunction "GND_2") (pintype "passive"))
      (node (ref "IC3") (pin "9") (pinfunction "EP_9") (pintype "passive"))
      (node (ref "IC4") (pin "1") (pinfunction "~{OE}_1") (pintype "passive"))
      (node (ref "IC4") (pin "3") (pinfunction "GND_3") (pintype "passive"))
      (node (ref "IC5") (pin "11") (pinfunction "GND_11") (pintype "passive"))
      (node (ref "IC5") (pin "2") (pinfunction "GND_2") (pintype "passive"))
      (node (ref "IC5") (pin "5") (pinfunction "GND_5") (pintype "passive"))
      (node (ref "IC5") (pin "8") (pinfunction "GND_8") (pintype "passive"))
      (node (ref "J4") (pin "1") (pinfunction "GND_1") (pintype "passive"))
      (node (ref "J4") (pin "13") (pinfunction "GND_13") (pintype "passive"))
      (node (ref "J4") (pin "14") (pinfunction "GND_14") (pintype "passive"))
      (node (ref "J4") (pin "19") (pinfunction "GND_19") (pintype "passive"))
      (node (ref "J4") (pin "21") (pinfunction "SHIELD_21") (pintype "passive"))
      (node (ref "J4") (pin "22") (pinfunction "SHIELD_22") (pintype "passive"))
      (node (ref "J4") (pin "23") (pinfunction "SHIELD_23") (pintype "passive"))
      (node (ref "J4") (pin "24") (pinfunction "SHIELD_24") (pintype "passive"))
      (node (ref "J4") (pin "7") (pinfunction "GND_7") (pintype "passive"))
      (node (ref "J4") (pin "8") (pinfunction "GND_8") (pintype "passive"))
      (node (ref "L1") (pin "1") (pintype "passive"))
      (node (ref "R34") (pin "1") (pintype "passive"))
      (node (ref "R35") (pin "1") (pintype "passive"))
      (node (ref "R43") (pin "1") (pintype "passive"))
      (node (ref "R44") (pin "1") (pintype "passive"))
      (node (ref "R45") (pin "1") (pintype "passive"))
      (node (ref "R48") (pin "2") (pintype "passive"))
      (node (ref "R49") (pin "1") (pintype "passive"))
      (node (ref "T1") (pin "2") (pinfunction "S_2") (pintype "passive"))
    )
    (net (code "63") (name "HDMI_PWR") (class "Default")
      (node (ref "C27") (pin "2") (pinfunction "2_2") (pintype "passive"))
      (node (ref "D1") (pin "A") (pinfunction "A_A") (pintype "passive"))
      (node (ref "IC2") (pin "13") (pinfunction "VCC_13") (pintype "passive"))
      (node (ref "IC2") (pin "14") (pinfunction "VCC_14") (pintype "passive"))
      (node (ref "IC3") (pin "6") (pinfunction "VCCB_6") (pintype "passive"))
      (node (ref "L2") (pin "2") (pintype "passive"))
      (node (ref "R39") (pin "2") (pintype "passive"))
      (node (ref "R40") (pin "2") (pintype "passive"))
    )
    (net (code "64") (name "HDMI_SHIELD") (class "Default")
      (node (ref "J3") (pin "1") (pinfunction "TMDS_Data2_Shield_1") (pintype "passive"))
      (node (ref "J3") (pin "10") (pinfunction "TMDS_Clock_Shield_10") (pintype "passive"))
      (node (ref "J3") (pin "4") (pinfunction "TMDS_Data1_Shield_4") (pintype "passive"))
      (node (ref "J3") (pin "7") (pinfunction "TMDS_Data0_Shield_7") (pintype "passive"))
      (node (ref "J3") (pin "Shell") (pinfunction "Shield_Shell") (pintype "passive"))
      (node (ref "L1") (pin "2") (pintype "passive"))
    )
    (net (code "65") (name "Net-(IC3-SCLA)") (class "Default")
      (node (ref "IC3") (pin "8") (pinfunction "SCLA_8") (pintype "passive"))
      (node (ref "R37") (pin "1") (pintype "passive"))
      (node (ref "R41") (pin "1") (pintype "passive"))
    )
    (net (code "66") (name "Net-(IC3-SDAA)") (class "Default")
      (node (ref "IC3") (pin "1") (pinfunction "SDAA_1") (pintype "passive"))
      (node (ref "R38") (pin "1") (pintype "passive"))
      (node (ref "R42") (pin "1") (pintype "passive"))
    )
    (net (code "67") (name "Net-(J3-+5V_Power)") (class "Default")
      (node (ref "C12") (pin "2") (pinfunction "2_2") (pintype "passive"))
      (node (ref "C13") (pin "2") (pinfunction "2_2") (pintype "passive"))
      (node (ref "D1") (pin "C") (pinfunction "C_C") (pintype "passive"))
      (node (ref "J3") (pin "18") (pinfunction "+5V_Power_18") (pintype "passive"))
    )
    (net (code "68") (name "Net-(J3-DDC_{slash}_CEC_Ground_{slash}_HEAC_Shield)") (class "Default")
      (node (ref "J3") (pin "13") (pinfunction "DDC_/_CEC_Ground_/_HEAC_Shield_13") (pintype "passive"))
      (node (ref "R34") (pin "2") (pintype "passive"))
    )
    (net (code "69") (name "Net-(J4-CONFIG2)") (class "Default")
      (node (ref "J4") (pin "6") (pinfunction "CONFIG2_6") (pintype "passive"))
      (node (ref "R45") (pin "2") (pintype "passive"))
    )
    (net (code "70") (name "Net-(J4-DP_PWR)") (class "Default")
      (node (ref "C18") (pin "2") (pinfunction "2_2") (pintype "passive"))
      (node (ref "C19") (pin "2") (pinfunction "2_2") (pintype "passive"))
      (node (ref "D2") (pin "C") (pinfunction "C_C") (pintype "passive"))
      (node (ref "J4") (pin "20") (pinfunction "DP_PWR_20") (pintype "passive"))
    )
    (net (code "71") (name "Net-(M1E-GPIO07)") (class "Default")
      (node (ref "M1") (pin "206") (pinfunction "GPIO07_206") (pintype "passive"))
      (node (ref "TP13") (pin "1") (pintype "passive"))
    )
    (net (code "72") (name "Net-(M1E-GPIO10)") (class "Default")
      (node (ref "M1") (pin "212") (pinfunction "GPIO10_212") (pintype "passive"))
      (node (ref "TP12") (pin "1") (pintype "passive"))
    )
    (net (code "73") (name "Net-(M1E-GPIO12)") (class "Default")
      (node (ref "M1") (pin "218") (pinfunction "GPIO12_218") (pintype "passive"))
      (node (ref "TP14") (pin "1") (pintype "passive"))
    )
    (net (code "74") (name "Net-(T1-G)") (class "Default")
      (node (ref "R47") (pin "2") (pintype "passive"))
      (node (ref "R49") (pin "2") (pintype "passive"))
      (node (ref "T1") (pin "1") (pinfunction "G_1") (pintype "passive"))
    )
    (net (code "75") (name "unconnected-(D4-IO1-Pad1)") (class "Default")
      (node (ref "D4") (pin "1") (pinfunction "IO1_1") (pintype "passive+no_connect"))
    )
    (net (code "76") (name "unconnected-(IC3-EN-Pad3)") (class "Default")
      (node (ref "IC3") (pin "3") (pinfunction "EN_3") (pintype "passive+no_connect"))
    )
    (net (code "77") (name "unconnected-(J3-Utility_{slash}_HEAC+-Pad17)") (class "Default")
      (node (ref "J3") (pin "17") (pinfunction "Utility_/_HEAC+_17") (pintype "passive+no_connect"))
    )
    (net (code "78") (name "unconnected-(M1E-CLK_32K_OUT-Pad210)") (class "Default")
      (node (ref "M1") (pin "210") (pinfunction "CLK_32K_OUT_210") (pintype "passive"))
    )
  )
)
